# MCU098_03_XDS110_Debug_Probe.net
KiCad netlist of a schematic drawn in Altium Designer
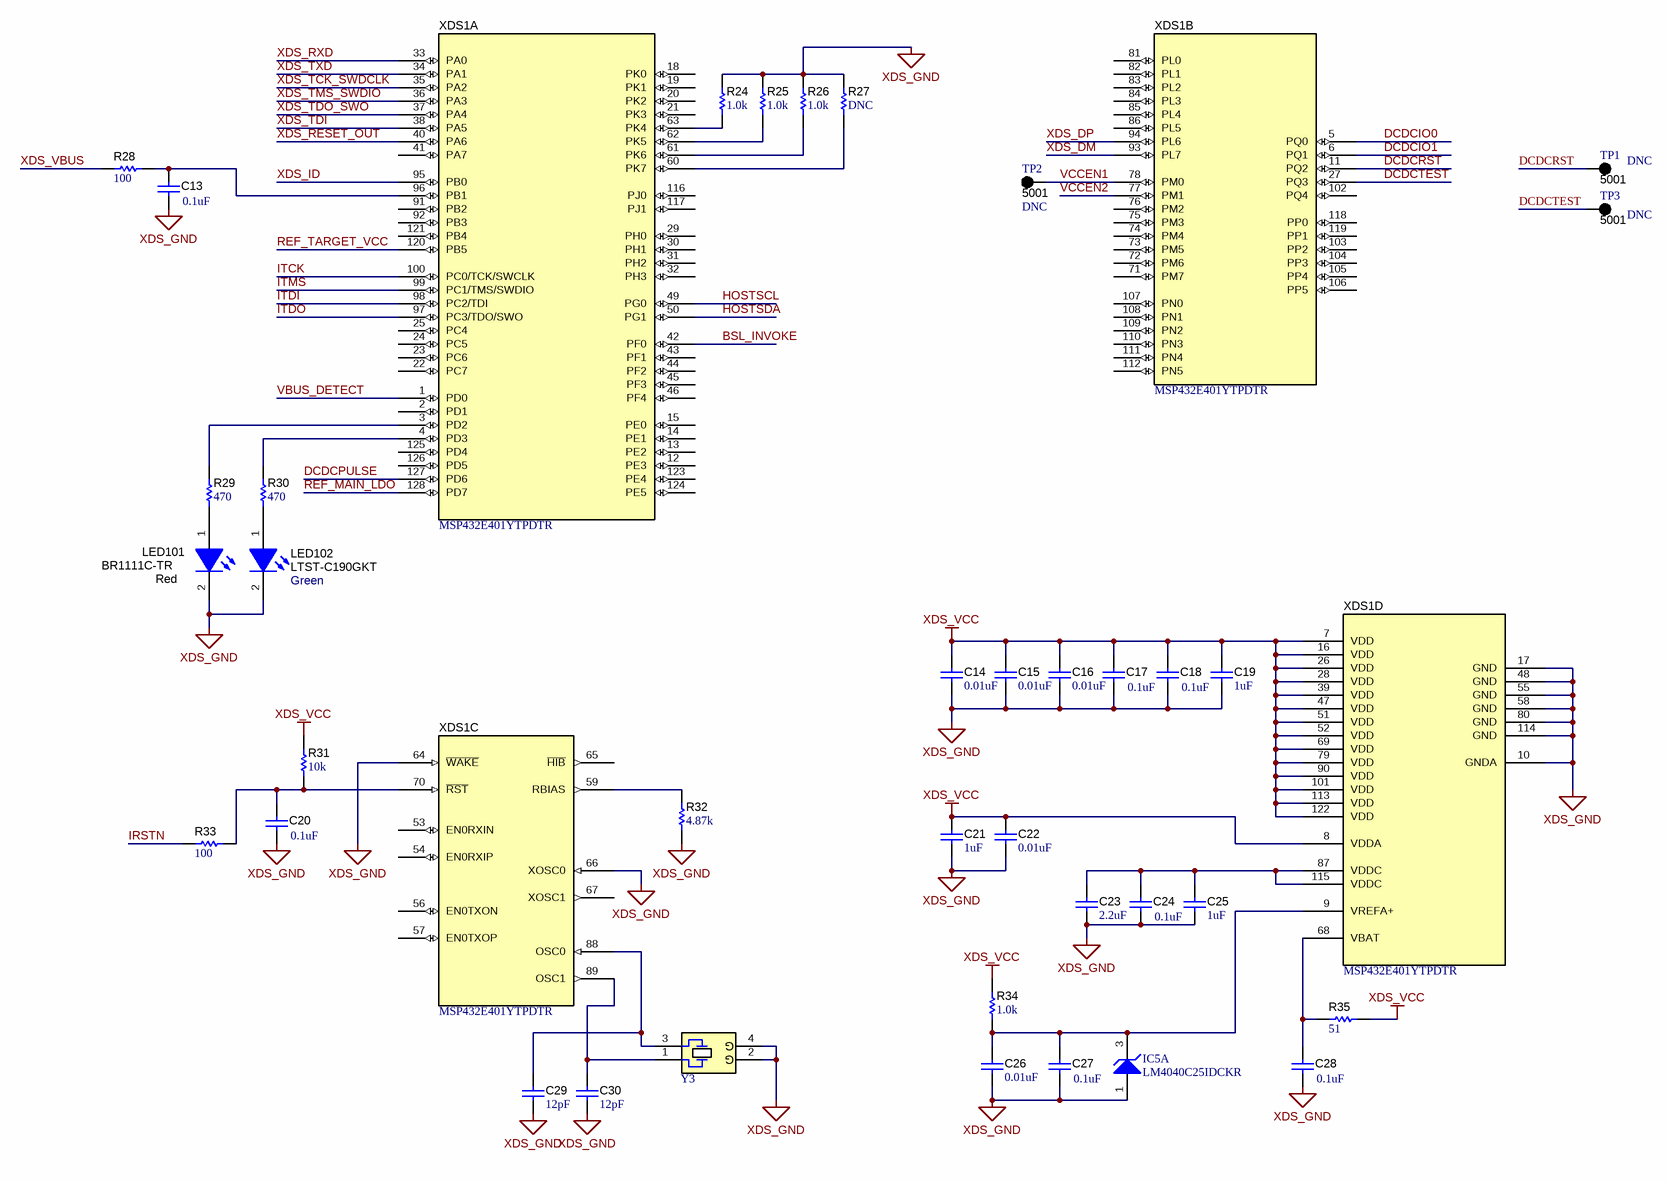
[diagram p0: MCU098_03_XDS110_Debug_Probe.SchDoc]

(export (version "E")
  (design (tool "Eeschema 10.0.6"))
  (components
    (comp (ref "C13")
      (value "GRM155R70J104KA01D")
      (footprint "0402")
      (description "CAP, CERM, 0.1 uF, 6.3 V, +/- 10%, X7R, 0402")
      (fields
        (field (name "MANUFACTURER") "MuRata")
        (field (name "VALUEDISPLAYED") "0.1uF")
        (field (name "PUBLISHER") "Texas Instruments")
      )
      (libsource (lib "Altium Vault - TI") (part "Capacitor"))
    )
    (comp (ref "C14")
      (value "GRM155R71E103KA01D")
      (footprint "0402")
      (description "CAP, CERM, 0.01 uF, 25 V, +/- 10%, X7R, 0402")
      (fields
        (field (name "MANUFACTURER") "MuRata")
        (field (name "VALUEDISPLAYED") "0.01uF")
        (field (name "PUBLISHER") "Texas Instruments")
      )
      (libsource (lib "Altium Vault - TI") (part "Capacitor"))
    )
    (comp (ref "C15")
      (value "GRM155R71E103KA01D")
      (footprint "0402")
      (description "CAP, CERM, 0.01 uF, 25 V, +/- 10%, X7R, 0402")
      (fields
        (field (name "MANUFACTURER") "MuRata")
        (field (name "VALUEDISPLAYED") "0.01uF")
        (field (name "PUBLISHER") "Texas Instruments")
      )
      (libsource (lib "Altium Vault - TI") (part "Capacitor"))
    )
    (comp (ref "C16")
      (value "GRM155R71E103KA01D")
      (footprint "0402")
      (description "CAP, CERM, 0.01 uF, 25 V, +/- 10%, X7R, 0402")
      (fields
        (field (name "MANUFACTURER") "MuRata")
        (field (name "VALUEDISPLAYED") "0.01uF")
        (field (name "PUBLISHER") "Texas Instruments")
      )
      (libsource (lib "Altium Vault - TI") (part "Capacitor"))
    )
    (comp (ref "C17")
      (value "GRM155R70J104KA01D")
      (footprint "0402")
      (description "CAP, CERM, 0.1 uF, 6.3 V, +/- 10%, X7R, 0402")
      (fields
        (field (name "MANUFACTURER") "MuRata")
        (field (name "VALUEDISPLAYED") "0.1uF")
        (field (name "PUBLISHER") "Texas Instruments")
      )
      (libsource (lib "Altium Vault - TI") (part "Capacitor"))
    )
    (comp (ref "C18")
      (value "GRM155R70J104KA01D")
      (footprint "0402")
      (description "CAP, CERM, 0.1 uF, 6.3 V, +/- 10%, X7R, 0402")
      (fields
        (field (name "MANUFACTURER") "MuRata")
        (field (name "VALUEDISPLAYED") "0.1uF")
        (field (name "PUBLISHER") "Texas Instruments")
      )
      (libsource (lib "Altium Vault - TI") (part "Capacitor"))
    )
    (comp (ref "C19")
      (value "C1005X5R1E105K050BC")
      (footprint "0402")
      (description "CAP, CERM, 1 uF, 25 V, +/- 10%, X5R, 0402")
      (fields
        (field (name "MANUFACTURER") "TDK")
        (field (name "VALUEDISPLAYED") "1uF")
        (field (name "PUBLISHER") "Texas Instruments")
      )
      (libsource (lib "Altium Vault - TI") (part "Capacitor"))
    )
    (comp (ref "C20")
      (value "GRM155R70J104KA01D")
      (footprint "0402")
      (description "CAP, CERM, 0.1 uF, 6.3 V, +/- 10%, X7R, 0402")
      (fields
        (field (name "MANUFACTURER") "MuRata")
        (field (name "VALUEDISPLAYED") "0.1uF")
        (field (name "PUBLISHER") "Texas Instruments")
      )
      (libsource (lib "Altium Vault - TI") (part "Capacitor"))
    )
    (comp (ref "C21")
      (value "C1005X5R1E105K050BC")
      (footprint "0402")
      (description "CAP, CERM, 1 uF, 25 V, +/- 10%, X5R, 0402")
      (fields
        (field (name "MANUFACTURER") "TDK")
        (field (name "VALUEDISPLAYED") "1uF")
        (field (name "PUBLISHER") "Texas Instruments")
      )
      (libsource (lib "Altium Vault - TI") (part "Capacitor"))
    )
    (comp (ref "C22")
      (value "GRM155R71E103KA01D")
      (footprint "0402")
      (description "CAP, CERM, 0.01 uF, 25 V, +/- 10%, X7R, 0402")
      (fields
        (field (name "MANUFACTURER") "MuRata")
        (field (name "VALUEDISPLAYED") "0.01uF")
        (field (name "PUBLISHER") "Texas Instruments")
      )
      (libsource (lib "Altium Vault - TI") (part "Capacitor"))
    )
    (comp (ref "C23")
      (value "GRM155R60J225KE95D")
      (footprint "0402")
      (description "CAP, CERM, 2.2 uF, 6.3 V, +/- 10%, X5R, 0402")
      (fields
        (field (name "MANUFACTURER") "MuRata")
        (field (name "VALUEDISPLAYED") "2.2uF")
        (field (name "PUBLISHER") "Texas Instruments")
      )
      (libsource (lib "Altium Vault - TI") (part "Capacitor"))
    )
    (comp (ref "C24")
      (value "GRM155R70J104KA01D")
      (footprint "0402")
      (description "CAP, CERM, 0.1 uF, 6.3 V, +/- 10%, X7R, 0402")
      (fields
        (field (name "MANUFACTURER") "MuRata")
        (field (name "VALUEDISPLAYED") "0.1uF")
        (field (name "PUBLISHER") "Texas Instruments")
      )
      (libsource (lib "Altium Vault - TI") (part "Capacitor"))
    )
    (comp (ref "C25")
      (value "C1005X5R1E105K050BC")
      (footprint "0402")
      (description "CAP, CERM, 1 uF, 25 V, +/- 10%, X5R, 0402")
      (fields
        (field (name "MANUFACTURER") "TDK")
        (field (name "VALUEDISPLAYED") "1uF")
        (field (name "PUBLISHER") "Texas Instruments")
      )
      (libsource (lib "Altium Vault - TI") (part "Capacitor"))
    )
    (comp (ref "C26")
      (value "GRM155R71E103KA01D")
      (footprint "0402")
      (description "CAP, CERM, 0.01 uF, 25 V, +/- 10%, X7R, 0402")
      (fields
        (field (name "MANUFACTURER") "MuRata")
        (field (name "VALUEDISPLAYED") "0.01uF")
        (field (name "PUBLISHER") "Texas Instruments")
      )
      (libsource (lib "Altium Vault - TI") (part "Capacitor"))
    )
    (comp (ref "C27")
      (value "GRM155R70J104KA01D")
      (footprint "0402")
      (description "CAP, CERM, 0.1 uF, 6.3 V, +/- 10%, X7R, 0402")
      (fields
        (field (name "MANUFACTURER") "MuRata")
        (field (name "VALUEDISPLAYED") "0.1uF")
        (field (name "PUBLISHER") "Texas Instruments")
      )
      (libsource (lib "Altium Vault - TI") (part "Capacitor"))
    )
    (comp (ref "C28")
      (value "GRM155R70J104KA01D")
      (footprint "0402")
      (description "CAP, CERM, 0.1 uF, 6.3 V, +/- 10%, X7R, 0402")
      (fields
        (field (name "MANUFACTURER") "MuRata")
        (field (name "VALUEDISPLAYED") "0.1uF")
        (field (name "PUBLISHER") "Texas Instruments")
      )
      (libsource (lib "Altium Vault - TI") (part "Capacitor"))
    )
    (comp (ref "C29")
      (value "GRM1555C1H120JA01D")
      (footprint "0402")
      (description "CAP, CERM, 12 pF, 50 V, +/- 5%, C0G/NP0, 0402")
      (fields
        (field (name "MANUFACTURER") "MuRata")
        (field (name "VALUEDISPLAYED") "12pF")
        (field (name "PUBLISHER") "Texas Instruments")
      )
      (libsource (lib "Altium Vault - TI") (part "Capacitor"))
    )
    (comp (ref "C30")
      (value "GRM1555C1H120JA01D")
      (footprint "0402")
      (description "CAP, CERM, 12 pF, 50 V, +/- 5%, C0G/NP0, 0402")
      (fields
        (field (name "MANUFACTURER") "MuRata")
        (field (name "VALUEDISPLAYED") "12pF")
        (field (name "PUBLISHER") "Texas Instruments")
      )
      (libsource (lib "Altium Vault - TI") (part "Capacitor"))
    )
    (comp (ref "IC5")
      (value "LM4040C25IDCKR")
      (footprint "DCK0005A_N")
      (fields (field (name "MANUFACTURER") "Texas Instruments") (field (name "PARTNUMBER") "LM4040C25IDCKR"))
      (libsource (lib "Altium Vault - TI") (part "TI-LM4040C25DCK5"))
    )
    (comp (ref "LED101")
      (value "BR1111C-TR")
      (footprint "1111C_Red")
      (description "LED, Red, SMD")
      (fields (field (name "ALTIUM_VALUE") "Red") (field (name "MANUFACTURER") "Stanley Electric Co., LTD"))
      (libsource (lib "Altium Vault - TI") (part "LED"))
    )
    (comp (ref "LED102")
      (value "LTST-C190GKT")
      (footprint "LED_LTST-C190")
      (description "LED, Green, SMD")
      (fields (field (name "ALTIUM_VALUE") "Green") (field (name "MANUFACTURER") "Lite-On"))
      (libsource (lib "Altium Vault - TI") (part "LED"))
    )
    (comp (ref "R24")
      (value "CRCW04021K00JNED")
      (footprint "0402")
      (description "RES, 1.0 k, 5%, 0.063 W, 0402")
      (fields
        (field (name "MANUFACTURER") "Vishay-Dale")
        (field (name "VALUEDISPLAYED") "1.0k")
        (field (name "PUBLISHER") "Texas Instruments")
      )
      (libsource (lib "Altium Vault - TI") (part "Resistor"))
    )
    (comp (ref "R25")
      (value "CRCW04021K00JNED")
      (footprint "0402")
      (description "RES, 1.0 k, 5%, 0.063 W, 0402")
      (fields
        (field (name "MANUFACTURER") "Vishay-Dale")
        (field (name "VALUEDISPLAYED") "1.0k")
        (field (name "PUBLISHER") "Texas Instruments")
      )
      (libsource (lib "Altium Vault - TI") (part "Resistor"))
    )
    (comp (ref "R26")
      (value "CRCW04021K00JNED")
      (footprint "0402")
      (description "RES, 1.0 k, 5%, 0.063 W, 0402")
      (fields
        (field (name "MANUFACTURER") "Vishay-Dale")
        (field (name "VALUEDISPLAYED") "1.0k")
        (field (name "PUBLISHER") "Texas Instruments")
      )
      (libsource (lib "Altium Vault - TI") (part "Resistor"))
    )
    (comp (ref "R27")
      (value "CRCW04021K00JNED")
      (footprint "0402")
      (description "RES, 1.0 k, 5%, 0.063 W, 0402")
      (fields
        (field (name "MANUFACTURER") "Vishay-Dale")
        (field (name "VALUEDISPLAYED") "DNC")
        (field (name "PUBLISHER") "Texas Instruments")
      )
      (libsource (lib "Altium Vault - TI") (part "Resistor"))
    )
    (comp (ref "R28")
      (value "CRCW0402100RJNED")
      (footprint "0402")
      (description "RES, 100, 5%, 0.063 W, AEC-Q200 Grade 0, 0402")
      (fields (field (name "MANUFACTURER") "Vishay-Dale") (field (name "VALUEDISPLAYED") "100"))
      (libsource (lib "Altium Vault - TI") (part "Resistor"))
    )
    (comp (ref "R29")
      (value "CRCW0402470RJNED")
      (footprint "0402")
      (description "RES, 470, 5%, 0.063 W, 0402")
      (fields
        (field (name "MANUFACTURER") "Vishay-Dale")
        (field (name "VALUEDISPLAYED") "470")
        (field (name "PUBLISHER") "Texas Instruments")
      )
      (libsource (lib "Altium Vault - TI") (part "Resistor"))
    )
    (comp (ref "R30")
      (value "CRCW0402470RJNED")
      (footprint "0402")
      (description "RES, 470, 5%, 0.063 W, 0402")
      (fields
        (field (name "MANUFACTURER") "Vishay-Dale")
        (field (name "VALUEDISPLAYED") "470")
        (field (name "PUBLISHER") "Texas Instruments")
      )
      (libsource (lib "Altium Vault - TI") (part "Resistor"))
    )
    (comp (ref "R31")
      (value "CRCW040210K0JNED")
      (footprint "0402")
      (description "RES, 10 k, 5%, 0.063 W, 0402")
      (fields
        (field (name "MANUFACTURER") "Vishay-Dale")
        (field (name "VALUEDISPLAYED") "10k")
        (field (name "PUBLISHER") "Texas Instruments")
      )
      (libsource (lib "Altium Vault - TI") (part "Resistor"))
    )
    (comp (ref "R32")
      (value "CRCW04024K87FKED")
      (footprint "0402")
      (description "RES, 4.87 k, 1%, 0.063 W, AEC-Q200 Grade 0, 0402")
      (fields (field (name "MANUFACTURER") "Vishay-Dale") (field (name "VALUEDISPLAYED") "4.87k"))
      (libsource (lib "Altium Vault - TI") (part "Resistor"))
    )
    (comp (ref "R33")
      (value "CRCW0402100RJNED")
      (footprint "0402")
      (description "RES, 100, 5%, 0.063 W, 0402")
      (fields
        (field (name "MANUFACTURER") "Vishay-Dale")
        (field (name "VALUEDISPLAYED") "100")
        (field (name "PUBLISHER") "Texas Instruments")
      )
      (libsource (lib "Altium Vault - TI") (part "Resistor"))
    )
    (comp (ref "R34")
      (value "CRCW04021K00JNED")
      (footprint "0402")
      (description "RES, 1.0 k, 5%, 0.063 W, 0402")
      (fields
        (field (name "MANUFACTURER") "Vishay-Dale")
        (field (name "VALUEDISPLAYED") "1.0k")
        (field (name "PUBLISHER") "Texas Instruments")
      )
      (libsource (lib "Altium Vault - TI") (part "Resistor"))
    )
    (comp (ref "R35")
      (value "CRCW040251R0JNED")
      (footprint "0402")
      (description "RES, 51, 5%, 0.063 W, AEC-Q200 Grade 0, 0402")
      (fields (field (name "MANUFACTURER") "Vishay-Dale") (field (name "VALUEDISPLAYED") "51"))
      (libsource (lib "Altium Vault - TI") (part "Resistor"))
    )
    (comp (ref "TP1")
      (value "5001")
      (footprint "Keystone5001")
      (description "Test Point, Miniature, Black, TH")
      (fields
        (field (name "MANUFACTURER") "Keystone")
        (field (name "DISPLAY") "DNC")
        (field (name "PUBLISHER") "Texas Instruments")
      )
      (libsource (lib "Altium Vault - TI") (part "5001"))
    )
    (comp (ref "TP2")
      (value "5001")
      (footprint "Keystone5001")
      (description "Test Point, Miniature, Black, TH")
      (fields
        (field (name "MANUFACTURER") "Keystone")
        (field (name "DISPLAY") "DNC")
        (field (name "PUBLISHER") "Texas Instruments")
      )
      (libsource (lib "Altium Vault - TI") (part "5001"))
    )
    (comp (ref "TP3")
      (value "5001")
      (footprint "Keystone5001")
      (description "Test Point, Miniature, Black, TH")
      (fields
        (field (name "MANUFACTURER") "Keystone")
        (field (name "DISPLAY") "DNC")
        (field (name "PUBLISHER") "Texas Instruments")
      )
      (libsource (lib "Altium Vault - TI") (part "5001"))
    )
    (comp (ref "XDS1")
      (value "MSP432E401YTPDTR")
      (footprint "PDT0128A")
      (description "MSP432E401YTPDT, PDT0128A (TQFP-128)")
      (fields
        (field (name "ALTERNATE PARTNUMBER") "MSP432E401YTPDT")
        (field (name "MANUFACTURER") "Texas Instruments")
        (field (name "PARTNUMBER") "MSP432E401YTPDTR")
      )
      (libsource (lib "Altium Vault - TI") (part "MSP432E401YTPDT"))
    )
    (comp (ref "Y3")
      (value "NX3225GA-16.000M-STD-CRG-1")
      (footprint "NDK_NX3225GA")
      (description "Crystal, 16 MHz, 8pF, SMD")
      (fields (field (name "MANUFACTURER") "NDK") (field (name "PUBLISHER") "Texas Instruments"))
      (libsource (lib "Altium Vault - TI") (part "XTAL_4P_13_G24"))
    )
  )
  (nets
    (net (code "1") (name "/BSL_INVOKE") (class "Default")
      (node (ref "XDS1") (pin "42") (pinfunction "PF0_42") (pintype "bidirectional"))
    )
    (net (code "2") (name "/DCDCIO0") (class "Default")
      (node (ref "XDS1") (pin "5") (pinfunction "PQ0_5") (pintype "bidirectional"))
    )
    (net (code "3") (name "/DCDCIO1") (class "Default")
      (node (ref "XDS1") (pin "6") (pinfunction "PQ1_6") (pintype "bidirectional"))
    )
    (net (code "4") (name "/DCDCPULSE") (class "Default")
      (node (ref "XDS1") (pin "127") (pinfunction "PD6_127") (pintype "bidirectional"))
    )
    (net (code "5") (name "/DCDCRST") (class "Default")
      (node (ref "TP1") (pin "1") (pintype "passive"))
      (node (ref "XDS1") (pin "11") (pinfunction "PQ2_11") (pintype "bidirectional"))
    )
    (net (code "6") (name "/DCDCTEST") (class "Default")
      (node (ref "TP3") (pin "1") (pintype "passive"))
      (node (ref "XDS1") (pin "27") (pinfunction "PQ3_27") (pintype "bidirectional"))
    )
    (net (code "7") (name "/HOSTSCL") (class "Default")
      (node (ref "XDS1") (pin "49") (pinfunction "PG0_49") (pintype "bidirectional"))
    )
    (net (code "8") (name "/HOSTSDA") (class "Default")
      (node (ref "XDS1") (pin "50") (pinfunction "PG1_50") (pintype "bidirectional"))
    )
    (net (code "9") (name "/IRSTN") (class "Default")
      (node (ref "R33") (pin "1") (pinfunction "1_1") (pintype "passive"))
    )
    (net (code "10") (name "/ITCK") (class "Default")
      (node (ref "XDS1") (pin "100") (pinfunction "PC0/TCK/SWCLK_100") (pintype "bidirectional"))
    )
    (net (code "11") (name "/ITDI") (class "Default")
      (node (ref "XDS1") (pin "98") (pinfunction "PC2/TDI_98") (pintype "bidirectional"))
    )
    (net (code "12") (name "/ITDO") (class "Default")
      (node (ref "XDS1") (pin "97") (pinfunction "PC3/TDO/SWO_97") (pintype "bidirectional"))
    )
    (net (code "13") (name "/ITMS") (class "Default")
      (node (ref "XDS1") (pin "99") (pinfunction "PC1/TMS/SWDIO_99") (pintype "bidirectional"))
    )
    (net (code "14") (name "/REF_MAIN_LDO") (class "Default")
      (node (ref "XDS1") (pin "128") (pinfunction "PD7_128") (pintype "bidirectional"))
    )
    (net (code "15") (name "/REF_TARGET_VCC") (class "Default")
      (node (ref "XDS1") (pin "120") (pinfunction "PB5_120") (pintype "bidirectional"))
    )
    (net (code "16") (name "/VBUS_DETECT") (class "Default")
      (node (ref "XDS1") (pin "1") (pinfunction "PD0_1") (pintype "bidirectional"))
    )
    (net (code "17") (name "/VCCEN1") (class "Default")
      (node (ref "TP2") (pin "1") (pintype "passive"))
      (node (ref "XDS1") (pin "78") (pinfunction "PM0_78") (pintype "bidirectional"))
    )
    (net (code "18") (name "/VCCEN2") (class "Default")
      (node (ref "XDS1") (pin "77") (pinfunction "PM1_77") (pintype "bidirectional"))
    )
    (net (code "19") (name "/XDS_DM") (class "Default")
      (node (ref "XDS1") (pin "93") (pinfunction "PL7_93") (pintype "bidirectional"))
    )
    (net (code "20") (name "/XDS_DP") (class "Default")
      (node (ref "XDS1") (pin "94") (pinfunction "PL6_94") (pintype "bidirectional"))
    )
    (net (code "21") (name "/XDS_ID") (class "Default")
      (node (ref "XDS1") (pin "95") (pinfunction "PB0_95") (pintype "bidirectional"))
    )
    (net (code "22") (name "/XDS_RESET_OUT") (class "Default")
      (node (ref "XDS1") (pin "40") (pinfunction "PA6_40") (pintype "bidirectional"))
    )
    (net (code "23") (name "/XDS_RXD") (class "Default")
      (node (ref "XDS1") (pin "33") (pinfunction "PA0_33") (pintype "bidirectional"))
    )
    (net (code "24") (name "/XDS_TCK_SWDCLK") (class "Default")
      (node (ref "XDS1") (pin "35") (pinfunction "PA2_35") (pintype "bidirectional"))
    )
    (net (code "25") (name "/XDS_TDI") (class "Default")
      (node (ref "XDS1") (pin "38") (pinfunction "PA5_38") (pintype "bidirectional"))
    )
    (net (code "26") (name "/XDS_TDO_SWO") (class "Default")
      (node (ref "XDS1") (pin "37") (pinfunction "PA4_37") (pintype "bidirectional"))
    )
    (net (code "27") (name "/XDS_TMS_SWDIO") (class "Default")
      (node (ref "XDS1") (pin "36") (pinfunction "PA3_36") (pintype "bidirectional"))
    )
    (net (code "28") (name "/XDS_TXD") (class "Default")
      (node (ref "XDS1") (pin "34") (pinfunction "PA1_34") (pintype "bidirectional"))
    )
    (net (code "29") (name "/XDS_VBUS") (class "Default")
      (node (ref "R28") (pin "1") (pinfunction "1_1") (pintype "passive"))
    )
    (net (code "30") (name "Net-(C23-Pad1)") (class "Default")
      (node (ref "C23") (pin "1") (pinfunction "1_1") (pintype "passive"))
      (node (ref "C24") (pin "1") (pinfunction "1_1") (pintype "passive"))
      (node (ref "C25") (pin "1") (pinfunction "1_1") (pintype "passive"))
      (node (ref "XDS1") (pin "115") (pinfunction "VDDC_115") (pintype "power_in"))
      (node (ref "XDS1") (pin "87") (pinfunction "VDDC_87") (pintype "power_in"))
    )
    (net (code "31") (name "Net-(IC5A-CATHODE)") (class "Default")
      (node (ref "C26") (pin "1") (pinfunction "1_1") (pintype "passive"))
      (node (ref "C27") (pin "1") (pinfunction "1_1") (pintype "passive"))
      (node (ref "IC5") (pin "3") (pinfunction "CATHODE_3") (pintype "passive"))
      (node (ref "R34") (pin "1") (pinfunction "1_1") (pintype "passive"))
      (node (ref "XDS1") (pin "9") (pinfunction "VREFA+_9") (pintype "power_in"))
    )
    (net (code "32") (name "Net-(LED101-A)") (class "Default")
      (node (ref "LED101") (pin "1") (pinfunction "A_1") (pintype "passive"))
      (node (ref "R29") (pin "1") (pinfunction "1_1") (pintype "passive"))
    )
    (net (code "33") (name "Net-(LED102-A)") (class "Default")
      (node (ref "LED102") (pin "1") (pinfunction "A_1") (pintype "passive"))
      (node (ref "R30") (pin "1") (pinfunction "1_1") (pintype "passive"))
    )
    (net (code "34") (name "Net-(XDS1A-PB1)") (class "Default")
      (node (ref "C13") (pin "1") (pinfunction "1_1") (pintype "passive"))
      (node (ref "R28") (pin "2") (pinfunction "2_2") (pintype "passive"))
      (node (ref "XDS1") (pin "96") (pinfunction "PB1_96") (pintype "bidirectional"))
    )
    (net (code "35") (name "Net-(XDS1A-PD2)") (class "Default")
      (node (ref "R29") (pin "2") (pinfunction "2_2") (pintype "passive"))
      (node (ref "XDS1") (pin "3") (pinfunction "PD2_3") (pintype "bidirectional"))
    )
    (net (code "36") (name "Net-(XDS1A-PD3)") (class "Default")
      (node (ref "R30") (pin "2") (pinfunction "2_2") (pintype "passive"))
      (node (ref "XDS1") (pin "4") (pinfunction "PD3_4") (pintype "bidirectional"))
    )
    (net (code "37") (name "Net-(XDS1A-PK4)") (class "Default")
      (node (ref "R24") (pin "1") (pinfunction "1_1") (pintype "passive"))
      (node (ref "XDS1") (pin "63") (pinfunction "PK4_63") (pintype "bidirectional"))
    )
    (net (code "38") (name "Net-(XDS1A-PK5)") (class "Default")
      (node (ref "R25") (pin "1") (pinfunction "1_1") (pintype "passive"))
      (node (ref "XDS1") (pin "62") (pinfunction "PK5_62") (pintype "bidirectional"))
    )
    (net (code "39") (name "Net-(XDS1A-PK6)") (class "Default")
      (node (ref "R26") (pin "1") (pinfunction "1_1") (pintype "passive"))
      (node (ref "XDS1") (pin "61") (pinfunction "PK6_61") (pintype "bidirectional"))
    )
    (net (code "40") (name "Net-(XDS1A-PK7)") (class "Default")
      (node (ref "R27") (pin "1") (pinfunction "1_1") (pintype "passive"))
      (node (ref "XDS1") (pin "60") (pinfunction "PK7_60") (pintype "bidirectional"))
    )
    (net (code "41") (name "Net-(XDS1C-OSC0)") (class "Default")
      (node (ref "C29") (pin "1") (pinfunction "1_1") (pintype "passive"))
      (node (ref "XDS1") (pin "88") (pinfunction "OSC0_88") (pintype "input"))
      (node (ref "Y3") (pin "3") (pinfunction "3_3") (pintype "passive"))
    )
    (net (code "42") (name "Net-(XDS1C-OSC1)") (class "Default")
      (node (ref "C30") (pin "1") (pinfunction "1_1") (pintype "passive"))
      (node (ref "XDS1") (pin "89") (pinfunction "OSC1_89") (pintype "output"))
      (node (ref "Y3") (pin "1") (pinfunction "1_1") (pintype "passive"))
    )
    (net (code "43") (name "Net-(XDS1C-RBIAS)") (class "Default")
      (node (ref "R32") (pin "2") (pinfunction "2_2") (pintype "passive"))
      (node (ref "XDS1") (pin "59") (pinfunction "RBIAS_59") (pintype "output"))
    )
    (net (code "44") (name "Net-(XDS1C-RST)") (class "Default")
      (node (ref "C20") (pin "1") (pinfunction "1_1") (pintype "passive"))
      (node (ref "R31") (pin "1") (pinfunction "1_1") (pintype "passive"))
      (node (ref "R33") (pin "2") (pinfunction "2_2") (pintype "passive"))
      (node (ref "XDS1") (pin "70") (pinfunction "RST_70") (pintype "input"))
    )
    (net (code "45") (name "Net-(XDS1D-VBAT)") (class "Default")
      (node (ref "C28") (pin "1") (pinfunction "1_1") (pintype "passive"))
      (node (ref "R35") (pin "1") (pinfunction "1_1") (pintype "passive"))
      (node (ref "XDS1") (pin "68") (pinfunction "VBAT_68") (pintype "power_in"))
    )
    (net (code "46") (name "XDS_GND") (class "Default")
      (node (ref "C13") (pin "2") (pinfunction "2_2") (pintype "passive"))
      (node (ref "C14") (pin "2") (pinfunction "2_2") (pintype "passive"))
      (node (ref "C15") (pin "2") (pinfunction "2_2") (pintype "passive"))
      (node (ref "C16") (pin "2") (pinfunction "2_2") (pintype "passive"))
      (node (ref "C17") (pin "2") (pinfunction "2_2") (pintype "passive"))
      (node (ref "C18") (pin "2") (pinfunction "2_2") (pintype "passive"))
      (node (ref "C19") (pin "2") (pinfunction "2_2") (pintype "passive"))
      (node (ref "C20") (pin "2") (pinfunction "2_2") (pintype "passive"))
      (node (ref "C21") (pin "2") (pinfunction "2_2") (pintype "passive"))
      (node (ref "C22") (pin "2") (pinfunction "2_2") (pintype "passive"))
      (node (ref "C23") (pin "2") (pinfunction "2_2") (pintype "passive"))
      (node (ref "C24") (pin "2") (pinfunction "2_2") (pintype "passive"))
      (node (ref "C25") (pin "2") (pinfunction "2_2") (pintype "passive"))
      (node (ref "C26") (pin "2") (pinfunction "2_2") (pintype "passive"))
      (node (ref "C27") (pin "2") (pinfunction "2_2") (pintype "passive"))
      (node (ref "C28") (pin "2") (pinfunction "2_2") (pintype "passive"))
      (node (ref "C29") (pin "2") (pinfunction "2_2") (pintype "passive"))
      (node (ref "C30") (pin "2") (pinfunction "2_2") (pintype "passive"))
      (node (ref "IC5") (pin "1") (pinfunction "ANODE_1") (pintype "passive"))
      (node (ref "LED101") (pin "2") (pinfunction "K_2") (pintype "passive"))
      (node (ref "LED102") (pin "2") (pinfunction "K_2") (pintype "passive"))
      (node (ref "R24") (pin "2") (pinfunction "2_2") (pintype "passive"))
      (node (ref "R25") (pin "2") (pinfunction "2_2") (pintype "passive"))
      (node (ref "R26") (pin "2") (pinfunction "2_2") (pintype "passive"))
      (node (ref "R27") (pin "2") (pinfunction "2_2") (pintype "passive"))
      (node (ref "R32") (pin "1") (pinfunction "1_1") (pintype "passive"))
      (node (ref "XDS1") (pin "10") (pinfunction "GNDA_10") (pintype "power_in"))
      (node (ref "XDS1") (pin "114") (pinfunction "GND_114") (pintype "power_in"))
      (node (ref "XDS1") (pin "17") (pinfunction "GND_17") (pintype "power_in"))
      (node (ref "XDS1") (pin "48") (pinfunction "GND_48") (pintype "power_in"))
      (node (ref "XDS1") (pin "55") (pinfunction "GND_55") (pintype "power_in"))
      (node (ref "XDS1") (pin "58") (pinfunction "GND_58") (pintype "power_in"))
      (node (ref "XDS1") (pin "64") (pinfunction "WAKE_64") (pintype "input"))
      (node (ref "XDS1") (pin "66") (pinfunction "XOSC0_66") (pintype "input"))
      (node (ref "XDS1") (pin "80") (pinfunction "GND_80") (pintype "power_in"))
      (node (ref "Y3") (pin "2") (pinfunction "GND_2") (pintype "power_in"))
      (node (ref "Y3") (pin "4") (pinfunction "GND_4") (pintype "power_in"))
    )
    (net (code "47") (name "XDS_VCC") (class "Default")
      (node (ref "C14") (pin "1") (pinfunction "1_1") (pintype "passive"))
      (node (ref "C15") (pin "1") (pinfunction "1_1") (pintype "passive"))
      (node (ref "C16") (pin "1") (pinfunction "1_1") (pintype "passive"))
      (node (ref "C17") (pin "1") (pinfunction "1_1") (pintype "passive"))
      (node (ref "C18") (pin "1") (pinfunction "1_1") (pintype "passive"))
      (node (ref "C19") (pin "1") (pinfunction "1_1") (pintype "passive"))
      (node (ref "C21") (pin "1") (pinfunction "1_1") (pintype "passive"))
      (node (ref "C22") (pin "1") (pinfunction "1_1") (pintype "passive"))
      (node (ref "R31") (pin "2") (pinfunction "2_2") (pintype "passive"))
      (node (ref "R34") (pin "2") (pinfunction "2_2") (pintype "passive"))
      (node (ref "R35") (pin "2") (pinfunction "2_2") (pintype "passive"))
      (node (ref "XDS1") (pin "101") (pinfunction "VDD_101") (pintype "power_in"))
      (node (ref "XDS1") (pin "113") (pinfunction "VDD_113") (pintype "power_in"))
      (node (ref "XDS1") (pin "122") (pinfunction "VDD_122") (pintype "power_in"))
      (node (ref "XDS1") (pin "16") (pinfunction "VDD_16") (pintype "power_in"))
      (node (ref "XDS1") (pin "26") (pinfunction "VDD_26") (pintype "power_in"))
      (node (ref "XDS1") (pin "28") (pinfunction "VDD_28") (pintype "power_in"))
      (node (ref "XDS1") (pin "39") (pinfunction "VDD_39") (pintype "power_in"))
      (node (ref "XDS1") (pin "47") (pinfunction "VDD_47") (pintype "power_in"))
      (node (ref "XDS1") (pin "51") (pinfunction "VDD_51") (pintype "power_in"))
      (node (ref "XDS1") (pin "52") (pinfunction "VDD_52") (pintype "power_in"))
      (node (ref "XDS1") (pin "69") (pinfunction "VDD_69") (pintype "power_in"))
      (node (ref "XDS1") (pin "7") (pinfunction "VDD_7") (pintype "power_in"))
      (node (ref "XDS1") (pin "79") (pinfunction "VDD_79") (pintype "power_in"))
      (node (ref "XDS1") (pin "8") (pinfunction "VDDA_8") (pintype "power_in"))
      (node (ref "XDS1") (pin "90") (pinfunction "VDD_90") (pintype "power_in"))
    )
    (net (code "48") (name "unconnected-(XDS1A-PA7-Pad41)") (class "Default")
      (node (ref "XDS1") (pin "41") (pinfunction "PA7_41") (pintype "bidirectional"))
    )
    (net (code "49") (name "unconnected-(XDS1A-PB2-Pad91)") (class "Default")
      (node (ref "XDS1") (pin "91") (pinfunction "PB2_91") (pintype "bidirectional"))
    )
    (net (code "50") (name "unconnected-(XDS1A-PB3-Pad92)") (class "Default")
      (node (ref "XDS1") (pin "92") (pinfunction "PB3_92") (pintype "bidirectional"))
    )
    (net (code "51") (name "unconnected-(XDS1A-PB4-Pad121)") (class "Default")
      (node (ref "XDS1") (pin "121") (pinfunction "PB4_121") (pintype "bidirectional"))
    )
    (net (code "52") (name "unconnected-(XDS1A-PC4-Pad25)") (class "Default")
      (node (ref "XDS1") (pin "25") (pinfunction "PC4_25") (pintype "bidirectional"))
    )
    (net (code "53") (name "unconnected-(XDS1A-PC5-Pad24)") (class "Default")
      (node (ref "XDS1") (pin "24") (pinfunction "PC5_24") (pintype "bidirectional"))
    )
    (net (code "54") (name "unconnected-(XDS1A-PC6-Pad23)") (class "Default")
      (node (ref "XDS1") (pin "23") (pinfunction "PC6_23") (pintype "bidirectional"))
    )
    (net (code "55") (name "unconnected-(XDS1A-PC7-Pad22)") (class "Default")
      (node (ref "XDS1") (pin "22") (pinfunction "PC7_22") (pintype "bidirectional"))
    )
    (net (code "56") (name "unconnected-(XDS1A-PD1-Pad2)") (class "Default")
      (node (ref "XDS1") (pin "2") (pinfunction "PD1_2") (pintype "bidirectional"))
    )
    (net (code "57") (name "unconnected-(XDS1A-PD4-Pad125)") (class "Default")
      (node (ref "XDS1") (pin "125") (pinfunction "PD4_125") (pintype "bidirectional"))
    )
    (net (code "58") (name "unconnected-(XDS1A-PD5-Pad126)") (class "Default")
      (node (ref "XDS1") (pin "126") (pinfunction "PD5_126") (pintype "bidirectional"))
    )
    (net (code "59") (name "unconnected-(XDS1A-PE0-Pad15)") (class "Default")
      (node (ref "XDS1") (pin "15") (pinfunction "PE0_15") (pintype "bidirectional"))
    )
    (net (code "60") (name "unconnected-(XDS1A-PE1-Pad14)") (class "Default")
      (node (ref "XDS1") (pin "14") (pinfunction "PE1_14") (pintype "bidirectional"))
    )
    (net (code "61") (name "unconnected-(XDS1A-PE2-Pad13)") (class "Default")
      (node (ref "XDS1") (pin "13") (pinfunction "PE2_13") (pintype "bidirectional"))
    )
    (net (code "62") (name "unconnected-(XDS1A-PE3-Pad12)") (class "Default")
      (node (ref "XDS1") (pin "12") (pinfunction "PE3_12") (pintype "bidirectional"))
    )
    (net (code "63") (name "unconnected-(XDS1A-PE4-Pad123)") (class "Default")
      (node (ref "XDS1") (pin "123") (pinfunction "PE4_123") (pintype "bidirectional"))
    )
    (net (code "64") (name "unconnected-(XDS1A-PE5-Pad124)") (class "Default")
      (node (ref "XDS1") (pin "124") (pinfunction "PE5_124") (pintype "bidirectional"))
    )
    (net (code "65") (name "unconnected-(XDS1A-PF1-Pad43)") (class "Default")
      (node (ref "XDS1") (pin "43") (pinfunction "PF1_43") (pintype "bidirectional"))
    )
    (net (code "66") (name "unconnected-(XDS1A-PF2-Pad44)") (class "Default")
      (node (ref "XDS1") (pin "44") (pinfunction "PF2_44") (pintype "bidirectional"))
    )
    (net (code "67") (name "unconnected-(XDS1A-PF3-Pad45)") (class "Default")
      (node (ref "XDS1") (pin "45") (pinfunction "PF3_45") (pintype "bidirectional"))
    )
    (net (code "68") (name "unconnected-(XDS1A-PF4-Pad46)") (class "Default")
      (node (ref "XDS1") (pin "46") (pinfunction "PF4_46") (pintype "bidirectional"))
    )
    (net (code "69") (name "unconnected-(XDS1A-PH0-Pad29)") (class "Default")
      (node (ref "XDS1") (pin "29") (pinfunction "PH0_29") (pintype "bidirectional"))
    )
    (net (code "70") (name "unconnected-(XDS1A-PH1-Pad30)") (class "Default")
      (node (ref "XDS1") (pin "30") (pinfunction "PH1_30") (pintype "bidirectional"))
    )
    (net (code "71") (name "unconnected-(XDS1A-PH2-Pad31)") (class "Default")
      (node (ref "XDS1") (pin "31") (pinfunction "PH2_31") (pintype "bidirectional"))
    )
    (net (code "72") (name "unconnected-(XDS1A-PH3-Pad32)") (class "Default")
      (node (ref "XDS1") (pin "32") (pinfunction "PH3_32") (pintype "bidirectional"))
    )
    (net (code "73") (name "unconnected-(XDS1A-PJ0-Pad116)") (class "Default")
      (node (ref "XDS1") (pin "116") (pinfunction "PJ0_116") (pintype "bidirectional"))
    )
    (net (code "74") (name "unconnected-(XDS1A-PJ1-Pad117)") (class "Default")
      (node (ref "XDS1") (pin "117") (pinfunction "PJ1_117") (pintype "bidirectional"))
    )
    (net (code "75") (name "unconnected-(XDS1A-PK0-Pad18)") (class "Default")
      (node (ref "XDS1") (pin "18") (pinfunction "PK0_18") (pintype "bidirectional"))
    )
    (net (code "76") (name "unconnected-(XDS1A-PK1-Pad19)") (class "Default")
      (node (ref "XDS1") (pin "19") (pinfunction "PK1_19") (pintype "bidirectional"))
    )
    (net (code "77") (name "unconnected-(XDS1A-PK2-Pad20)") (class "Default")
      (node (ref "XDS1") (pin "20") (pinfunction "PK2_20") (pintype "bidirectional"))
    )
    (net (code "78") (name "unconnected-(XDS1A-PK3-Pad21)") (class "Default")
      (node (ref "XDS1") (pin "21") (pinfunction "PK3_21") (pintype "bidirectional"))
    )
    (net (code "79") (name "unconnected-(XDS1B-PL0-Pad81)") (class "Default")
      (node (ref "XDS1") (pin "81") (pinfunction "PL0_81") (pintype "bidirectional"))
    )
    (net (code "80") (name "unconnected-(XDS1B-PL1-Pad82)") (class "Default")
      (node (ref "XDS1") (pin "82") (pinfunction "PL1_82") (pintype "bidirectional"))
    )
    (net (code "81") (name "unconnected-(XDS1B-PL2-Pad83)") (class "Default")
      (node (ref "XDS1") (pin "83") (pinfunction "PL2_83") (pintype "bidirectional"))
    )
    (net (code "82") (name "unconnected-(XDS1B-PL3-Pad84)") (class "Default")
      (node (ref "XDS1") (pin "84") (pinfunction "PL3_84") (pintype "bidirectional"))
    )
    (net (code "83") (name "unconnected-(XDS1B-PL4-Pad85)") (class "Default")
      (node (ref "XDS1") (pin "85") (pinfunction "PL4_85") (pintype "bidirectional"))
    )
    (net (code "84") (name "unconnected-(XDS1B-PL5-Pad86)") (class "Default")
      (node (ref "XDS1") (pin "86") (pinfunction "PL5_86") (pintype "bidirectional"))
    )
    (net (code "85") (name "unconnected-(XDS1B-PM2-Pad76)") (class "Default")
      (node (ref "XDS1") (pin "76") (pinfunction "PM2_76") (pintype "bidirectional"))
    )
    (net (code "86") (name "unconnected-(XDS1B-PM3-Pad75)") (class "Default")
      (node (ref "XDS1") (pin "75") (pinfunction "PM3_75") (pintype "bidirectional"))
    )
    (net (code "87") (name "unconnected-(XDS1B-PM4-Pad74)") (class "Default")
      (node (ref "XDS1") (pin "74") (pinfunction "PM4_74") (pintype "bidirectional"))
    )
    (net (code "88") (name "unconnected-(XDS1B-PM5-Pad73)") (class "Default")
      (node (ref "XDS1") (pin "73") (pinfunction "PM5_73") (pintype "bidirectional"))
    )
    (net (code "89") (name "unconnected-(XDS1B-PM6-Pad72)") (class "Default")
      (node (ref "XDS1") (pin "72") (pinfunction "PM6_72") (pintype "bidirectional"))
    )
    (net (code "90") (name "unconnected-(XDS1B-PM7-Pad71)") (class "Default")
      (node (ref "XDS1") (pin "71") (pinfunction "PM7_71") (pintype "bidirectional"))
    )
    (net (code "91") (name "unconnected-(XDS1B-PN0-Pad107)") (class "Default")
      (node (ref "XDS1") (pin "107") (pinfunction "PN0_107") (pintype "bidirectional"))
    )
    (net (code "92") (name "unconnected-(XDS1B-PN1-Pad108)") (class "Default")
      (node (ref "XDS1") (pin "108") (pinfunction "PN1_108") (pintype "bidirectional"))
    )
    (net (code "93") (name "unconnected-(XDS1B-PN2-Pad109)") (class "Default")
      (node (ref "XDS1") (pin "109") (pinfunction "PN2_109") (pintype "bidirectional"))
    )
    (net (code "94") (name "unconnected-(XDS1B-PN3-Pad110)") (class "Default")
      (node (ref "XDS1") (pin "110") (pinfunction "PN3_110") (pintype "bidirectional"))
    )
    (net (code "95") (name "unconnected-(XDS1B-PN4-Pad111)") (class "Default")
      (node (ref "XDS1") (pin "111") (pinfunction "PN4_111") (pintype "bidirectional"))
    )
    (net (code "96") (name "unconnected-(XDS1B-PN5-Pad112)") (class "Default")
      (node (ref "XDS1") (pin "112") (pinfunction "PN5_112") (pintype "bidirectional"))
    )
    (net (code "97") (name "unconnected-(XDS1B-PP0-Pad118)") (class "Default")
      (node (ref "XDS1") (pin "118") (pinfunction "PP0_118") (pintype "bidirectional"))
    )
    (net (code "98") (name "unconnected-(XDS1B-PP1-Pad119)") (class "Default")
      (node (ref "XDS1") (pin "119") (pinfunction "PP1_119") (pintype "bidirectional"))
    )
    (net (code "99") (name "unconnected-(XDS1B-PP2-Pad103)") (class "Default")
      (node (ref "XDS1") (pin "103") (pinfunction "PP2_103") (pintype "bidirectional"))
    )
    (net (code "100") (name "unconnected-(XDS1B-PP3-Pad104)") (class "Default")
      (node (ref "XDS1") (pin "104") (pinfunction "PP3_104") (pintype "bidirectional"))
    )
    (net (code "101") (name "unconnected-(XDS1B-PP4-Pad105)") (class "Default")
      (node (ref "XDS1") (pin "105") (pinfunction "PP4_105") (pintype "bidirectional"))
    )
    (net (code "102") (name "unconnected-(XDS1B-PP5-Pad106)") (class "Default")
      (node (ref "XDS1") (pin "106") (pinfunction "PP5_106") (pintype "bidirectional"))
    )
    (net (code "103") (name "unconnected-(XDS1B-PQ4-Pad102)") (class "Default")
      (node (ref "XDS1") (pin "102") (pinfunction "PQ4_102") (pintype "bidirectional"))
    )
    (net (code "104") (name "unconnected-(XDS1C-EN0RXIN-Pad53)") (class "Default")
      (node (ref "XDS1") (pin "53") (pinfunction "EN0RXIN_53") (pintype "bidirectional"))
    )
    (net (code "105") (name "unconnected-(XDS1C-EN0RXIP-Pad54)") (class "Default")
      (node (ref "XDS1") (pin "54") (pinfunction "EN0RXIP_54") (pintype "bidirectional"))
    )
    (net (code "106") (name "unconnected-(XDS1C-EN0TXON-Pad56)") (class "Default")
      (node (ref "XDS1") (pin "56") (pinfunction "EN0TXON_56") (pintype "bidirectional"))
    )
    (net (code "107") (name "unconnected-(XDS1C-EN0TXOP-Pad57)") (class "Default")
      (node (ref "XDS1") (pin "57") (pinfunction "EN0TXOP_57") (pintype "bidirectional"))
    )
    (net (code "108") (name "unconnected-(XDS1C-HIB-Pad65)") (class "Default")
      (node (ref "XDS1") (pin "65") (pinfunction "HIB_65") (pintype "output"))
    )
    (net (code "109") (name "unconnected-(XDS1C-XOSC1-Pad67)") (class "Default")
      (node (ref "XDS1") (pin "67") (pinfunction "XOSC1_67") (pintype "output"))
    )
  )
)
